# MCU.net
KiCad netlist of a schematic drawn in Altium Designer
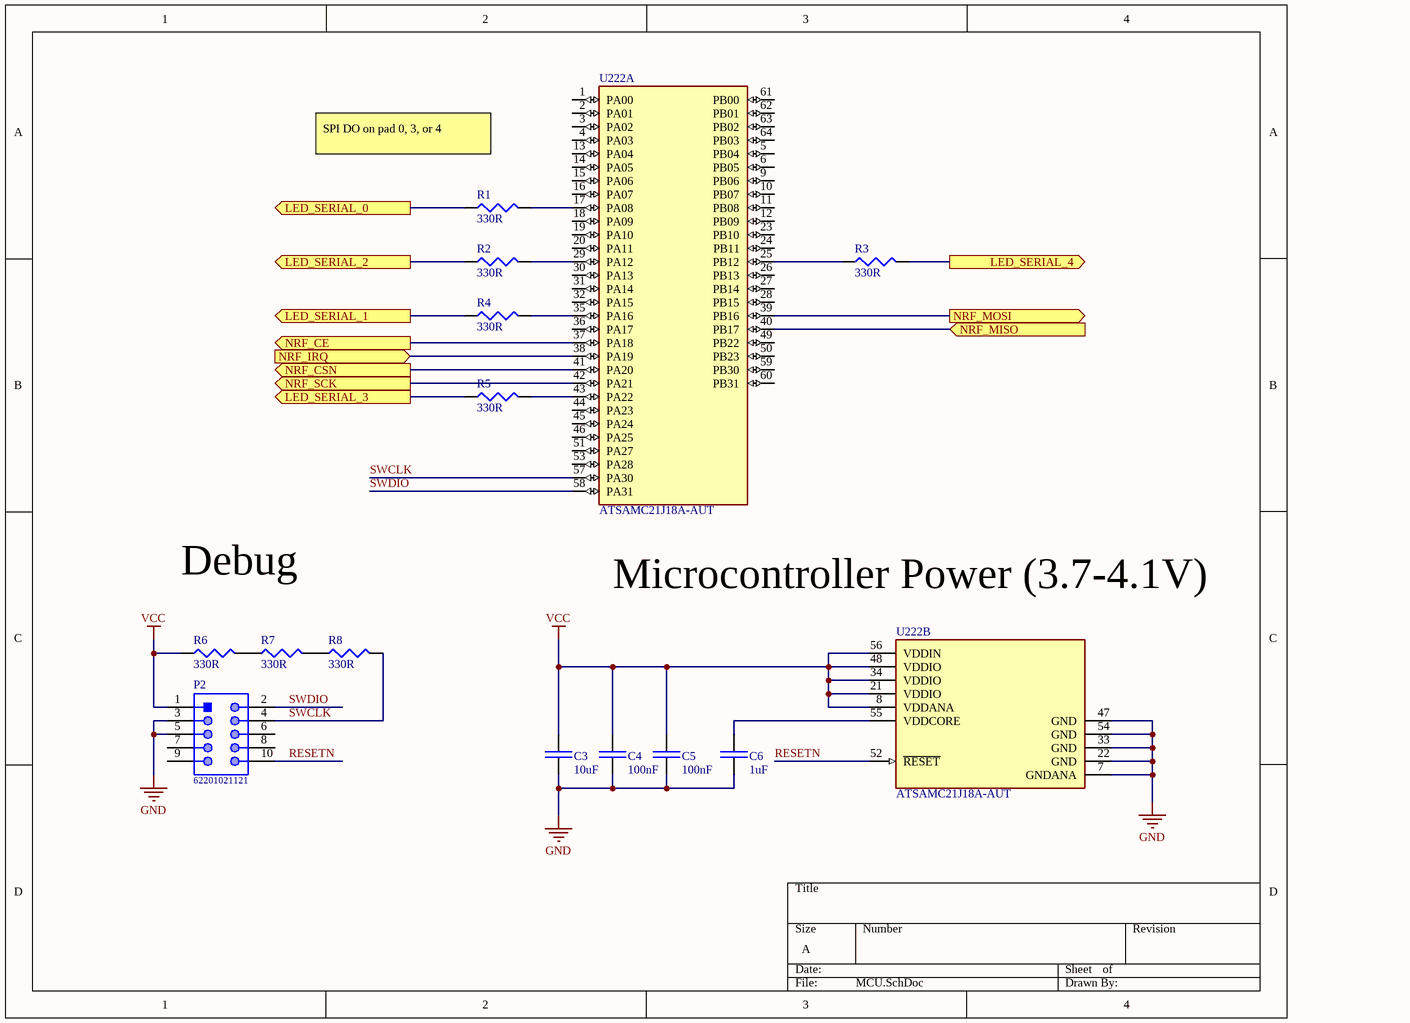
[diagram p0: MCU.SchDoc]

(export (version "E")
  (design (tool "Eeschema 10.0.6"))
  (components
    (comp (ref "C3")
      (value "10uF")
      (footprint "CAPC2012X14M")
      (description "MULTILAYER CERAMIC CAPACITORS MLCC - SMD/SMT 10UF 25V 0805 ROHS")
      (fields (field (name "LCSC PART #") "C15850"))
      (libsource (lib "Schlib1") (part "CL21A106KAYNNNE"))
    )
    (comp (ref "C4")
      (value "100nF")
      (footprint "CAPC1608X09M")
      (description "MULTILAYER CERAMIC CAPACITORS MLCC - SMD/SMT 100NF 50V 0603 ROHS")
      (fields (field (name "LCSC PART #") "C14663"))
      (libsource (lib "Schlib1") (part "CC0603KRX7R9BB104_1"))
    )
    (comp (ref "C5")
      (value "100nF")
      (footprint "CAPC1608X09M")
      (description "MULTILAYER CERAMIC CAPACITORS MLCC - SMD/SMT 100NF 50V 0603 ROHS")
      (fields (field (name "LCSC PART #") "C14663"))
      (libsource (lib "Schlib1") (part "CC0603KRX7R9BB104_1"))
    )
    (comp (ref "C6")
      (value "1uF")
      (footprint "CAPC2012X14M")
      (description "MULTILAYER CERAMIC CAPACITORS MLCC - SMD/SMT 1UF 50V 0805 ROHS")
      (fields (field (name "LCSC PART #") "C28323"))
      (libsource (lib "Schlib1") (part "CL21B105KBFNNNE_1"))
    )
    (comp (ref "P2")
      (value "62201021121")
      (footprint "62201021121")
      (description "THT Vertical Pin Header WR-PHD, Pitch 1.27 mm, Dual Row, 10 pins")
      (fields (field (name "MANUFACTURER") "Wurth Elektronik") (field (name "PUBLISHER") "WurthElektronik"))
      (libsource (lib "Altium Content Vault") (part "WE-CN-2P-M-R10"))
    )
    (comp (ref "R1")
      (value "330R")
      (footprint "RESC1608X06M")
      (description "CHIP RESISTOR - SURFACE MOUNT 330OHMS ±1% 1/10W 0603 ROHS")
      (fields (field (name "LCSC PART #") "C23138"))
      (libsource (lib "Schlib1") (part "0603WAF3300T5E"))
    )
    (comp (ref "R2")
      (value "330R")
      (footprint "RESC1608X06M")
      (description "CHIP RESISTOR - SURFACE MOUNT 330OHMS ±1% 1/10W 0603 ROHS")
      (fields (field (name "LCSC PART #") "C23138"))
      (libsource (lib "Schlib1") (part "0603WAF3300T5E"))
    )
    (comp (ref "R3")
      (value "330R")
      (footprint "RESC1608X06M")
      (description "CHIP RESISTOR - SURFACE MOUNT 330OHMS ±1% 1/10W 0603 ROHS")
      (fields (field (name "LCSC PART #") "C23138"))
      (libsource (lib "Schlib1") (part "0603WAF3300T5E"))
    )
    (comp (ref "R4")
      (value "330R")
      (footprint "RESC1608X06M")
      (description "CHIP RESISTOR - SURFACE MOUNT 330OHMS ±1% 1/10W 0603 ROHS")
      (fields (field (name "LCSC PART #") "C23138"))
      (libsource (lib "Schlib1") (part "0603WAF3300T5E"))
    )
    (comp (ref "R5")
      (value "330R")
      (footprint "RESC1608X06M")
      (description "CHIP RESISTOR - SURFACE MOUNT 330OHMS ±1% 1/10W 0603 ROHS")
      (fields (field (name "LCSC PART #") "C23138"))
      (libsource (lib "Schlib1") (part "0603WAF3300T5E"))
    )
    (comp (ref "R6")
      (value "330R")
      (footprint "RESC1608X06M")
      (description "CHIP RESISTOR - SURFACE MOUNT 330OHMS ±1% 1/10W 0603 ROHS")
      (fields (field (name "LCSC PART #") "C23138"))
      (libsource (lib "Schlib1") (part "0603WAF3300T5E"))
    )
    (comp (ref "R7")
      (value "330R")
      (footprint "RESC1608X06M")
      (description "CHIP RESISTOR - SURFACE MOUNT 330OHMS ±1% 1/10W 0603 ROHS")
      (fields (field (name "LCSC PART #") "C23138"))
      (libsource (lib "Schlib1") (part "0603WAF3300T5E"))
    )
    (comp (ref "R8")
      (value "330R")
      (footprint "RESC1608X06M")
      (description "CHIP RESISTOR - SURFACE MOUNT 330OHMS ±1% 1/10W 0603 ROHS")
      (fields (field (name "LCSC PART #") "C23138"))
      (libsource (lib "Schlib1") (part "0603WAF3300T5E"))
    )
    (comp (ref "U222")
      (value "ATSAMC21J18A-AUT")
      (footprint "TQFP64")
      (description "IC MCU 32BIT 256KB FLASH 64TQFP")
      (libsource (lib "Schlib1") (part "CMP-06276-000065-1"))
    )
  )
  (nets
    (net (code "1") (name "/LED_SERIAL_0") (class "Default") (node (ref "R1") (pin "1") (pintype "passive")))
    (net (code "2") (name "/LED_SERIAL_1") (class "Default") (node (ref "R4") (pin "1") (pintype "passive")))
    (net (code "3") (name "/LED_SERIAL_2") (class "Default") (node (ref "R2") (pin "1") (pintype "passive")))
    (net (code "4") (name "/LED_SERIAL_3") (class "Default") (node (ref "R5") (pin "1") (pintype "passive")))
    (net (code "5") (name "/LED_SERIAL_4") (class "Default") (node (ref "R3") (pin "2") (pintype "passive")))
    (net (code "6") (name "/NRF_CE") (class "Default")
      (node (ref "U222") (pin "37") (pinfunction "PA18_37") (pintype "bidirectional"))
    )
    (net (code "7") (name "/NRF_CSN") (class "Default")
      (node (ref "U222") (pin "41") (pinfunction "PA20_41") (pintype "bidirectional"))
    )
    (net (code "8") (name "/NRF_IRQ") (class "Default")
      (node (ref "U222") (pin "38") (pinfunction "PA19_38") (pintype "bidirectional"))
    )
    (net (code "9") (name "/NRF_MISO") (class "Default")
      (node (ref "U222") (pin "40") (pinfunction "PB17_40") (pintype "bidirectional"))
    )
    (net (code "10") (name "/NRF_MOSI") (class "Default")
      (node (ref "U222") (pin "39") (pinfunction "PB16_39") (pintype "bidirectional"))
    )
    (net (code "11") (name "/NRF_SCK") (class "Default")
      (node (ref "U222") (pin "42") (pinfunction "PA21_42") (pintype "bidirectional"))
    )
    (net (code "12") (name "/RESETN") (class "Default")
      (node (ref "P2") (pin "10") (pinfunction "10_10") (pintype "passive"))
      (node (ref "U222") (pin "52") (pinfunction "~{RESET}_52") (pintype "input"))
    )
    (net (code "13") (name "/SWCLK") (class "Default")
      (node (ref "P2") (pin "4") (pinfunction "4_4") (pintype "passive"))
      (node (ref "R8") (pin "2") (pintype "passive"))
      (node (ref "U222") (pin "57") (pinfunction "PA30_57") (pintype "bidirectional"))
    )
    (net (code "14") (name "/SWDIO") (class "Default")
      (node (ref "P2") (pin "2") (pinfunction "2_2") (pintype "passive"))
      (node (ref "U222") (pin "58") (pinfunction "PA31_58") (pintype "bidirectional"))
    )
    (net (code "15") (name "GND") (class "Default")
      (node (ref "C3") (pin "2") (pintype "passive"))
      (node (ref "C4") (pin "2") (pintype "passive"))
      (node (ref "C5") (pin "2") (pintype "passive"))
      (node (ref "C6") (pin "2") (pintype "passive"))
      (node (ref "P2") (pin "3") (pinfunction "3_3") (pintype "passive"))
      (node (ref "P2") (pin "5") (pinfunction "5_5") (pintype "passive"))
      (node (ref "U222") (pin "22") (pinfunction "GND_22") (pintype "power_in"))
      (node (ref "U222") (pin "33") (pinfunction "GND_33") (pintype "power_in"))
      (node (ref "U222") (pin "47") (pinfunction "GND_47") (pintype "power_in"))
      (node (ref "U222") (pin "54") (pinfunction "GND_54") (pintype "power_in"))
      (node (ref "U222") (pin "7") (pinfunction "GNDANA_7") (pintype "power_in"))
    )
    (net (code "16") (name "Net-(R6-Pad2)") (class "Default")
      (node (ref "R6") (pin "2") (pintype "passive"))
      (node (ref "R7") (pin "1") (pintype "passive"))
    )
    (net (code "17") (name "Net-(R7-Pad2)") (class "Default")
      (node (ref "R7") (pin "2") (pintype "passive"))
      (node (ref "R8") (pin "1") (pintype "passive"))
    )
    (net (code "18") (name "Net-(U222A-PA08)") (class "Default")
      (node (ref "R1") (pin "2") (pintype "passive"))
      (node (ref "U222") (pin "17") (pinfunction "PA08_17") (pintype "bidirectional"))
    )
    (net (code "19") (name "Net-(U222A-PA12)") (class "Default")
      (node (ref "R2") (pin "2") (pintype "passive"))
      (node (ref "U222") (pin "29") (pinfunction "PA12_29") (pintype "bidirectional"))
    )
    (net (code "20") (name "Net-(U222A-PA16)") (class "Default")
      (node (ref "R4") (pin "2") (pintype "passive"))
      (node (ref "U222") (pin "35") (pinfunction "PA16_35") (pintype "bidirectional"))
    )
    (net (code "21") (name "Net-(U222A-PA22)") (class "Default")
      (node (ref "R5") (pin "2") (pintype "passive"))
      (node (ref "U222") (pin "43") (pinfunction "PA22_43") (pintype "bidirectional"))
    )
    (net (code "22") (name "Net-(U222A-PB12)") (class "Default")
      (node (ref "R3") (pin "1") (pintype "passive"))
      (node (ref "U222") (pin "25") (pinfunction "PB12_25") (pintype "bidirectional"))
    )
    (net (code "23") (name "Net-(U222B-VDDCORE)") (class "Default")
      (node (ref "C6") (pin "1") (pintype "passive"))
      (node (ref "U222") (pin "55") (pinfunction "VDDCORE_55") (pintype "power_in"))
    )
    (net (code "24") (name "VCC") (class "Default")
      (node (ref "C3") (pin "1") (pintype "passive"))
      (node (ref "C4") (pin "1") (pintype "passive"))
      (node (ref "C5") (pin "1") (pintype "passive"))
      (node (ref "P2") (pin "1") (pinfunction "1_1") (pintype "passive"))
      (node (ref "R6") (pin "1") (pintype "passive"))
      (node (ref "U222") (pin "21") (pinfunction "VDDIO_21") (pintype "power_in"))
      (node (ref "U222") (pin "34") (pinfunction "VDDIO_34") (pintype "power_in"))
      (node (ref "U222") (pin "48") (pinfunction "VDDIO_48") (pintype "power_in"))
      (node (ref "U222") (pin "56") (pinfunction "VDDIN_56") (pintype "power_in"))
      (node (ref "U222") (pin "8") (pinfunction "VDDANA_8") (pintype "power_in"))
    )
    (net (code "25") (name "unconnected-(P2-Pad6)") (class "Default")
      (node (ref "P2") (pin "6") (pinfunction "6_6") (pintype "passive"))
    )
    (net (code "26") (name "unconnected-(P2-Pad7)") (class "Default")
      (node (ref "P2") (pin "7") (pinfunction "7_7") (pintype "passive"))
    )
    (net (code "27") (name "unconnected-(P2-Pad8)") (class "Default")
      (node (ref "P2") (pin "8") (pinfunction "8_8") (pintype "passive"))
    )
    (net (code "28") (name "unconnected-(P2-Pad9)") (class "Default")
      (node (ref "P2") (pin "9") (pinfunction "9_9") (pintype "passive"))
    )
    (net (code "29") (name "unconnected-(U222A-PA00-Pad1)") (class "Default")
      (node (ref "U222") (pin "1") (pinfunction "PA00_1") (pintype "bidirectional"))
    )
    (net (code "30") (name "unconnected-(U222A-PA01-Pad2)") (class "Default")
      (node (ref "U222") (pin "2") (pinfunction "PA01_2") (pintype "bidirectional"))
    )
    (net (code "31") (name "unconnected-(U222A-PA02-Pad3)") (class "Default")
      (node (ref "U222") (pin "3") (pinfunction "PA02_3") (pintype "bidirectional"))
    )
    (net (code "32") (name "unconnected-(U222A-PA03-Pad4)") (class "Default")
      (node (ref "U222") (pin "4") (pinfunction "PA03_4") (pintype "bidirectional"))
    )
    (net (code "33") (name "unconnected-(U222A-PA04-Pad13)") (class "Default")
      (node (ref "U222") (pin "13") (pinfunction "PA04_13") (pintype "bidirectional"))
    )
    (net (code "34") (name "unconnected-(U222A-PA05-Pad14)") (class "Default")
      (node (ref "U222") (pin "14") (pinfunction "PA05_14") (pintype "bidirectional"))
    )
    (net (code "35") (name "unconnected-(U222A-PA06-Pad15)") (class "Default")
      (node (ref "U222") (pin "15") (pinfunction "PA06_15") (pintype "bidirectional"))
    )
    (net (code "36") (name "unconnected-(U222A-PA07-Pad16)") (class "Default")
      (node (ref "U222") (pin "16") (pinfunction "PA07_16") (pintype "bidirectional"))
    )
    (net (code "37") (name "unconnected-(U222A-PA09-Pad18)") (class "Default")
      (node (ref "U222") (pin "18") (pinfunction "PA09_18") (pintype "bidirectional"))
    )
    (net (code "38") (name "unconnected-(U222A-PA10-Pad19)") (class "Default")
      (node (ref "U222") (pin "19") (pinfunction "PA10_19") (pintype "bidirectional"))
    )
    (net (code "39") (name "unconnected-(U222A-PA11-Pad20)") (class "Default")
      (node (ref "U222") (pin "20") (pinfunction "PA11_20") (pintype "bidirectional"))
    )
    (net (code "40") (name "unconnected-(U222A-PA13-Pad30)") (class "Default")
      (node (ref "U222") (pin "30") (pinfunction "PA13_30") (pintype "bidirectional"))
    )
    (net (code "41") (name "unconnected-(U222A-PA14-Pad31)") (class "Default")
      (node (ref "U222") (pin "31") (pinfunction "PA14_31") (pintype "bidirectional"))
    )
    (net (code "42") (name "unconnected-(U222A-PA15-Pad32)") (class "Default")
      (node (ref "U222") (pin "32") (pinfunction "PA15_32") (pintype "bidirectional"))
    )
    (net (code "43") (name "unconnected-(U222A-PA17-Pad36)") (class "Default")
      (node (ref "U222") (pin "36") (pinfunction "PA17_36") (pintype "bidirectional"))
    )
    (net (code "44") (name "unconnected-(U222A-PA23-Pad44)") (class "Default")
      (node (ref "U222") (pin "44") (pinfunction "PA23_44") (pintype "bidirectional"))
    )
    (net (code "45") (name "unconnected-(U222A-PA24-Pad45)") (class "Default")
      (node (ref "U222") (pin "45") (pinfunction "PA24_45") (pintype "bidirectional"))
    )
    (net (code "46") (name "unconnected-(U222A-PA25-Pad46)") (class "Default")
      (node (ref "U222") (pin "46") (pinfunction "PA25_46") (pintype "bidirectional"))
    )
    (net (code "47") (name "unconnected-(U222A-PA27-Pad51)") (class "Default")
      (node (ref "U222") (pin "51") (pinfunction "PA27_51") (pintype "bidirectional"))
    )
    (net (code "48") (name "unconnected-(U222A-PA28-Pad53)") (class "Default")
      (node (ref "U222") (pin "53") (pinfunction "PA28_53") (pintype "bidirectional"))
    )
    (net (code "49") (name "unconnected-(U222A-PB00-Pad61)") (class "Default")
      (node (ref "U222") (pin "61") (pinfunction "PB00_61") (pintype "bidirectional"))
    )
    (net (code "50") (name "unconnected-(U222A-PB01-Pad62)") (class "Default")
      (node (ref "U222") (pin "62") (pinfunction "PB01_62") (pintype "bidirectional"))
    )
    (net (code "51") (name "unconnected-(U222A-PB02-Pad63)") (class "Default")
      (node (ref "U222") (pin "63") (pinfunction "PB02_63") (pintype "bidirectional"))
    )
    (net (code "52") (name "unconnected-(U222A-PB03-Pad64)") (class "Default")
      (node (ref "U222") (pin "64") (pinfunction "PB03_64") (pintype "bidirectional"))
    )
    (net (code "53") (name "unconnected-(U222A-PB04-Pad5)") (class "Default")
      (node (ref "U222") (pin "5") (pinfunction "PB04_5") (pintype "bidirectional"))
    )
    (net (code "54") (name "unconnected-(U222A-PB05-Pad6)") (class "Default")
      (node (ref "U222") (pin "6") (pinfunction "PB05_6") (pintype "bidirectional"))
    )
    (net (code "55") (name "unconnected-(U222A-PB06-Pad9)") (class "Default")
      (node (ref "U222") (pin "9") (pinfunction "PB06_9") (pintype "bidirectional"))
    )
    (net (code "56") (name "unconnected-(U222A-PB07-Pad10)") (class "Default")
      (node (ref "U222") (pin "10") (pinfunction "PB07_10") (pintype "bidirectional"))
    )
    (net (code "57") (name "unconnected-(U222A-PB08-Pad11)") (class "Default")
      (node (ref "U222") (pin "11") (pinfunction "PB08_11") (pintype "bidirectional"))
    )
    (net (code "58") (name "unconnected-(U222A-PB09-Pad12)") (class "Default")
      (node (ref "U222") (pin "12") (pinfunction "PB09_12") (pintype "bidirectional"))
    )
    (net (code "59") (name "unconnected-(U222A-PB10-Pad23)") (class "Default")
      (node (ref "U222") (pin "23") (pinfunction "PB10_23") (pintype "bidirectional"))
    )
    (net (code "60") (name "unconnected-(U222A-PB11-Pad24)") (class "Default")
      (node (ref "U222") (pin "24") (pinfunction "PB11_24") (pintype "bidirectional"))
    )
    (net (code "61") (name "unconnected-(U222A-PB13-Pad26)") (class "Default")
      (node (ref "U222") (pin "26") (pinfunction "PB13_26") (pintype "bidirectional"))
    )
    (net (code "62") (name "unconnected-(U222A-PB14-Pad27)") (class "Default")
      (node (ref "U222") (pin "27") (pinfunction "PB14_27") (pintype "bidirectional"))
    )
    (net (code "63") (name "unconnected-(U222A-PB15-Pad28)") (class "Default")
      (node (ref "U222") (pin "28") (pinfunction "PB15_28") (pintype "bidirectional"))
    )
    (net (code "64") (name "unconnected-(U222A-PB22-Pad49)") (class "Default")
      (node (ref "U222") (pin "49") (pinfunction "PB22_49") (pintype "bidirectional"))
    )
    (net (code "65") (name "unconnected-(U222A-PB23-Pad50)") (class "Default")
      (node (ref "U222") (pin "50") (pinfunction "PB23_50") (pintype "bidirectional"))
    )
    (net (code "66") (name "unconnected-(U222A-PB30-Pad59)") (class "Default")
      (node (ref "U222") (pin "59") (pinfunction "PB30_59") (pintype "bidirectional"))
    )
    (net (code "67") (name "unconnected-(U222A-PB31-Pad60)") (class "Default")
      (node (ref "U222") (pin "60") (pinfunction "PB31_60") (pintype "bidirectional"))
    )
  )
)
